# 3.net
KiCad netlist of a schematic drawn in EasyEDA
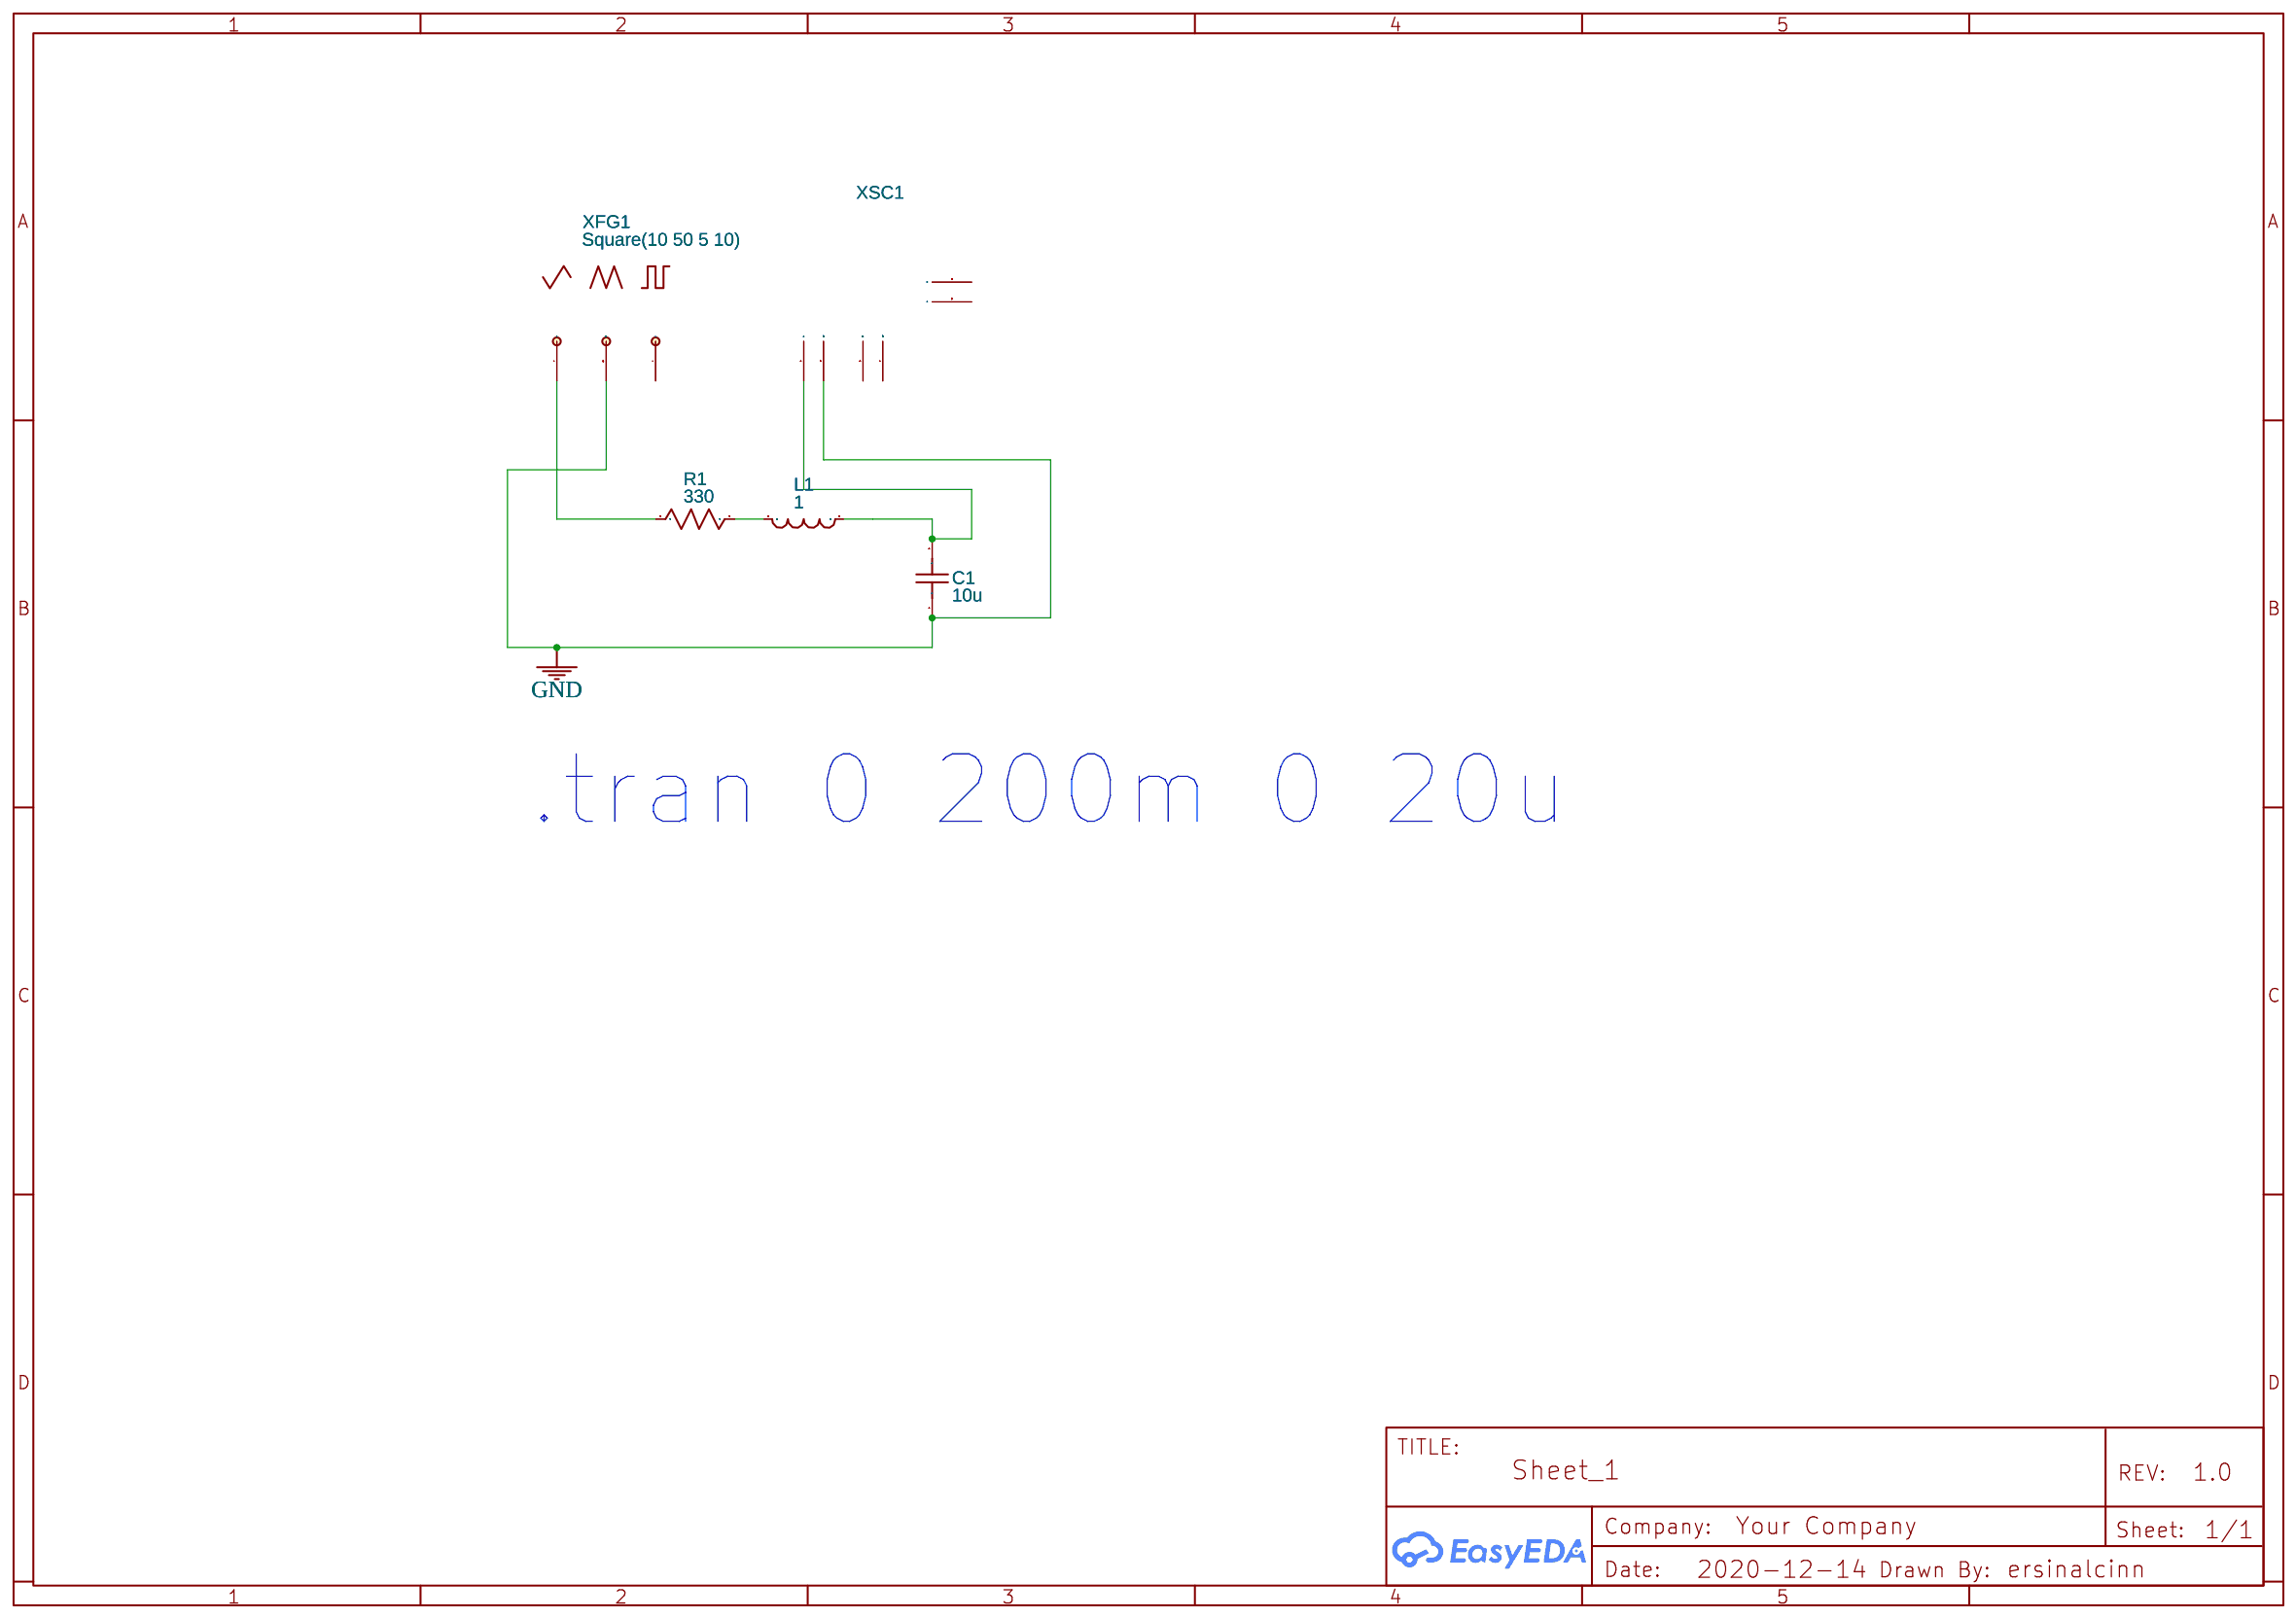
[diagram p0: schematic sheet]

(export (version "E")
  (design (tool "Eeschema 10.0.6"))
  (components
    (comp (ref "C1") (value "10u") (libsource (lib "") (part "Capacitor_US")))
    (comp (ref "L1") (value "1") (libsource (lib "") (part "Inductor")))
    (comp (ref "R1") (value "330") (libsource (lib "") (part "Resistor_US")))
    (comp (ref "XFG1") (value "Square(10 50 5 10)") (libsource (lib "") (part "FUNCTIONGENERATOR")))
    (comp (ref "XSC1") (value "Oscilloscope") (libsource (lib "") (part "OSCILLOSCOPE")))
  )
  (nets
    (net (code "1") (name "GND") (class "Default")
      (node (ref "C1") (pin "1") (pinfunction "1_1") (pintype "unspecified"))
      (node (ref "XFG1") (pin "COM") (pinfunction "COM_COM") (pintype "unspecified"))
      (node (ref "XSC1") (pin "2") (pinfunction "GND1_2") (pintype "unspecified"))
    )
    (net (code "2") (name "Net-(L1-Pad2)") (class "Default")
      (node (ref "L1") (pin "2") (pinfunction "2_2") (pintype "unspecified"))
      (node (ref "R1") (pin "2") (pinfunction "2_2") (pintype "unspecified"))
    )
    (net (code "3") (name "Net-(R1-Pad1)") (class "Default")
      (node (ref "R1") (pin "1") (pinfunction "1_1") (pintype "unspecified"))
      (node (ref "XFG1") (pin "+") (pinfunction "+_+") (pintype "unspecified"))
    )
    (net (code "4") (name "Net-(XSC1-A)") (class "Default")
      (node (ref "C1") (pin "2") (pinfunction "2_2") (pintype "unspecified"))
      (node (ref "L1") (pin "1") (pinfunction "1_1") (pintype "unspecified"))
      (node (ref "XSC1") (pin "1") (pinfunction "A_1") (pintype "unspecified"))
    )
    (net (code "5") (name "unconnected-(XFG1-Pad-)") (class "Default")
      (node (ref "XFG1") (pin "-") (pinfunction "-_-") (pintype "unspecified"))
    )
    (net (code "6") (name "unconnected-(XSC1-B-Pad3)") (class "Default")
      (node (ref "XSC1") (pin "3") (pinfunction "B_3") (pintype "unspecified"))
    )
    (net (code "7") (name "unconnected-(XSC1-GND2-Pad4)") (class "Default")
      (node (ref "XSC1") (pin "4") (pinfunction "GND2_4") (pintype "unspecified"))
    )
    (net (code "8") (name "unconnected-(XSC1-T+-Pad5)") (class "Default")
      (node (ref "XSC1") (pin "5") (pinfunction "T+_5") (pintype "unspecified"))
    )
    (net (code "9") (name "unconnected-(XSC1-T--Pad6)") (class "Default")
      (node (ref "XSC1") (pin "6") (pinfunction "T-_6") (pintype "unspecified"))
    )
  )
)
